# CW308T_PIC24FJ.net
KiCad netlist of a schematic drawn in Altium Designer
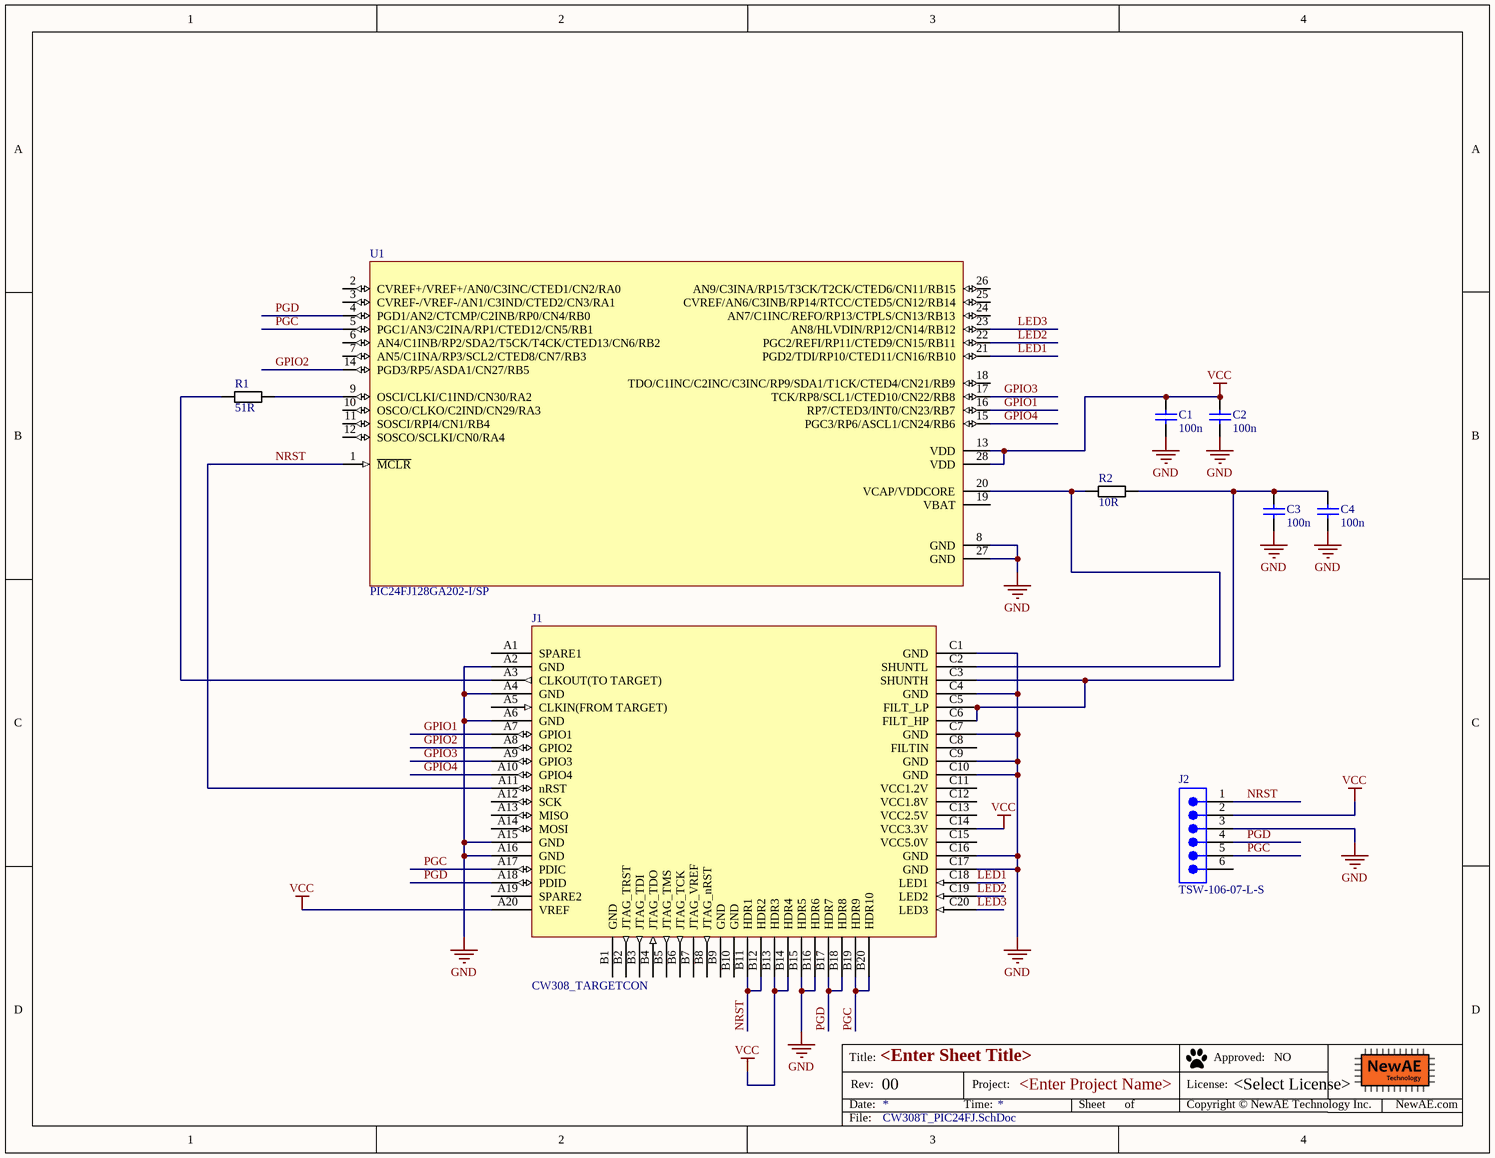
[diagram p0: CW308T_PIC24FJ.SchDoc]

(export (version "E")
  (design (tool "Eeschema 10.0.6"))
  (components
    (comp (ref "C1")
      (value "100n")
      (footprint "CAPC0603_M")
      (description "100n, 0603")
      (fields (field (name "PART NUMBER") "CCHIP-100n-0603"))
      (libsource (lib "NewAE_AltiumLib") (part "CAP"))
    )
    (comp (ref "C2")
      (value "100n")
      (footprint "CAPC0603_M")
      (description "100n, 0603")
      (fields (field (name "PART NUMBER") "CCHIP-100n-0603"))
      (libsource (lib "NewAE_AltiumLib") (part "CAP"))
    )
    (comp (ref "C3")
      (value "100n")
      (footprint "CAPC0603_M")
      (description "100n, 0603")
      (fields (field (name "PART NUMBER") "CCHIP-100n-0603"))
      (libsource (lib "NewAE_AltiumLib") (part "CAP"))
    )
    (comp (ref "C4")
      (value "100n")
      (footprint "CAPC0603_M")
      (description "100n, 0603")
      (fields (field (name "PART NUMBER") "CCHIP-100n-0603"))
      (libsource (lib "NewAE_AltiumLib") (part "CAP"))
    )
    (comp (ref "J1")
      (value "CW308_TARGETCON")
      (footprint "CW308_TBOARD_CONN")
      (description "CW308 \"Standard\" Target Board Connector")
      (fields (field (name "PART NUMBER") "CW308_TBOARD"))
      (libsource (lib "NewAE_AltiumLib") (part "CW308_TBOARD"))
    )
    (comp (ref "J2")
      (value "TSW-106-07-L-S")
      (footprint "SMTC-TSW-106-07-X-S")
      (fields (field (name "MANUFACTURER") "Samtec"))
      (libsource (lib "Altium Content Vault") (part "SMTC-TSW-106-X-X-S-X"))
    )
    (comp (ref "R1")
      (value "51R")
      (footprint "RESC1608X55N")
      (description "51R res, 0603, 1%, 1/10W")
      (fields (field (name "PART NUMBER") "RCHIP-51R-0603") (field (name "TOLERANCE") "1%"))
      (libsource (lib "NewAE_AltiumLib") (part "RES-EU"))
    )
    (comp (ref "R2")
      (value "10R")
      (footprint "RESC1608X55N")
      (description "10R res, 0603, 1%, 1/10W")
      (fields (field (name "PART NUMBER") "RCHIP-10R-0603") (field (name "TOLERANCE") "1%"))
      (libsource (lib "NewAE_AltiumLib") (part "RES-EU"))
    )
    (comp (ref "U1")
      (value "PIC24FJ128GA202-I/SP")
      (footprint "DIP28")
      (description "PIC24FJ, Hardware AES")
      (libsource (lib "NewAE_AltiumLib") (part "PIC24FJ128GA202_28pin"))
    )
  )
  (nets
    (net (code "1") (name "/GPIO1") (class "Default")
      (node (ref "J1") (pin "A7") (pinfunction "GPIO1_A7") (pintype "bidirectional"))
      (node (ref "U1") (pin "16") (pinfunction "RP7/CTED3/INT0/CN23/RB7_16") (pintype "bidirectional"))
    )
    (net (code "2") (name "/GPIO2") (class "Default")
      (node (ref "J1") (pin "A8") (pinfunction "GPIO2_A8") (pintype "bidirectional"))
      (node (ref "U1") (pin "14") (pinfunction "PGD3/RP5/ASDA1/CN27/RB5_14") (pintype "bidirectional"))
    )
    (net (code "3") (name "/GPIO3") (class "Default")
      (node (ref "J1") (pin "A9") (pinfunction "GPIO3_A9") (pintype "bidirectional"))
      (node (ref "U1") (pin "17") (pinfunction "TCK/RP8/SCL1/CTED10/CN22/RB8_17") (pintype "bidirectional"))
    )
    (net (code "4") (name "/GPIO4") (class "Default")
      (node (ref "J1") (pin "A10") (pinfunction "GPIO4_A10") (pintype "bidirectional"))
      (node (ref "U1") (pin "15") (pinfunction "PGC3/RP6/ASCL1/CN24/RB6_15") (pintype "bidirectional"))
    )
    (net (code "5") (name "/LED1") (class "Default")
      (node (ref "J1") (pin "C18") (pinfunction "LED1_C18") (pintype "input"))
      (node (ref "U1") (pin "21") (pinfunction "PGD2/TDI/RP10/CTED11/CN16/RB10_21") (pintype "bidirectional"))
    )
    (net (code "6") (name "/LED2") (class "Default")
      (node (ref "J1") (pin "C19") (pinfunction "LED2_C19") (pintype "input"))
      (node (ref "U1") (pin "22") (pinfunction "PGC2/REFI/RP11/CTED9/CN15/RB11_22") (pintype "bidirectional"))
    )
    (net (code "7") (name "/LED3") (class "Default")
      (node (ref "J1") (pin "C20") (pinfunction "LED3_C20") (pintype "input"))
      (node (ref "U1") (pin "23") (pinfunction "AN8/HLVDIN/RP12/CN14/RB12_23") (pintype "bidirectional"))
    )
    (net (code "8") (name "/NRST") (class "Default")
      (node (ref "J1") (pin "A11") (pinfunction "nRST_A11") (pintype "bidirectional"))
      (node (ref "J1") (pin "B11") (pinfunction "HDR1_B11") (pintype "passive"))
      (node (ref "J1") (pin "B12") (pinfunction "HDR2_B12") (pintype "passive"))
      (node (ref "J2") (pin "1") (pinfunction "1_1") (pintype "passive"))
      (node (ref "U1") (pin "1") (pinfunction "~{MCLR}_1") (pintype "input"))
    )
    (net (code "9") (name "/PGC") (class "Default")
      (node (ref "J1") (pin "A17") (pinfunction "PDIC_A17") (pintype "bidirectional"))
      (node (ref "J1") (pin "B19") (pinfunction "HDR9_B19") (pintype "passive"))
      (node (ref "J1") (pin "B20") (pinfunction "HDR10_B20") (pintype "passive"))
      (node (ref "J2") (pin "5") (pinfunction "5_5") (pintype "passive"))
      (node (ref "U1") (pin "5") (pinfunction "PGC1/AN3/C2INA/RP1/CTED12/CN5/RB1_5") (pintype "bidirectional"))
    )
    (net (code "10") (name "/PGD") (class "Default")
      (node (ref "J1") (pin "A18") (pinfunction "PDID_A18") (pintype "bidirectional"))
      (node (ref "J1") (pin "B17") (pinfunction "HDR7_B17") (pintype "passive"))
      (node (ref "J1") (pin "B18") (pinfunction "HDR8_B18") (pintype "passive"))
      (node (ref "J2") (pin "4") (pinfunction "4_4") (pintype "passive"))
      (node (ref "U1") (pin "4") (pinfunction "PGD1/AN2/CTCMP/C2INB/RP0/CN4/RB0_4") (pintype "bidirectional"))
    )
    (net (code "11") (name "GND") (class "Default")
      (node (ref "C1") (pin "2") (pinfunction "2_2") (pintype "passive"))
      (node (ref "C2") (pin "2") (pinfunction "2_2") (pintype "passive"))
      (node (ref "C3") (pin "2") (pinfunction "2_2") (pintype "passive"))
      (node (ref "C4") (pin "2") (pinfunction "2_2") (pintype "passive"))
      (node (ref "J1") (pin "A15") (pinfunction "GND_A15") (pintype "passive"))
      (node (ref "J1") (pin "A16") (pinfunction "GND_A16") (pintype "passive"))
      (node (ref "J1") (pin "A2") (pinfunction "GND_A2") (pintype "passive"))
      (node (ref "J1") (pin "A4") (pinfunction "GND_A4") (pintype "passive"))
      (node (ref "J1") (pin "A6") (pinfunction "GND_A6") (pintype "power_in"))
      (node (ref "J1") (pin "B15") (pinfunction "HDR5_B15") (pintype "passive"))
      (node (ref "J1") (pin "B16") (pinfunction "HDR6_B16") (pintype "passive"))
      (node (ref "J1") (pin "C1") (pinfunction "GND_C1") (pintype "power_in"))
      (node (ref "J1") (pin "C10") (pinfunction "GND_C10") (pintype "power_in"))
      (node (ref "J1") (pin "C16") (pinfunction "GND_C16") (pintype "power_in"))
      (node (ref "J1") (pin "C17") (pinfunction "GND_C17") (pintype "power_in"))
      (node (ref "J1") (pin "C4") (pinfunction "GND_C4") (pintype "power_in"))
      (node (ref "J1") (pin "C7") (pinfunction "GND_C7") (pintype "power_in"))
      (node (ref "J1") (pin "C9") (pinfunction "GND_C9") (pintype "power_in"))
      (node (ref "J2") (pin "3") (pinfunction "3_3") (pintype "passive"))
      (node (ref "U1") (pin "27") (pinfunction "GND_27") (pintype "power_in"))
      (node (ref "U1") (pin "8") (pinfunction "GND_8") (pintype "power_in"))
    )
    (net (code "12") (name "Net-(J1-CLKOUT(TO_TARGET))") (class "Default")
      (node (ref "J1") (pin "A3") (pinfunction "CLKOUT(TO_TARGET)_A3") (pintype "output"))
      (node (ref "R1") (pin "1") (pinfunction "1_1") (pintype "passive"))
    )
    (net (code "13") (name "Net-(J1-FILT_HP)") (class "Default")
      (node (ref "C3") (pin "1") (pinfunction "1_1") (pintype "passive"))
      (node (ref "C4") (pin "1") (pinfunction "1_1") (pintype "passive"))
      (node (ref "J1") (pin "C3") (pinfunction "SHUNTH_C3") (pintype "passive"))
      (node (ref "J1") (pin "C5") (pinfunction "FILT_LP_C5") (pintype "passive"))
      (node (ref "J1") (pin "C6") (pinfunction "FILT_HP_C6") (pintype "passive"))
      (node (ref "R2") (pin "2") (pinfunction "2_2") (pintype "passive"))
    )
    (net (code "14") (name "Net-(J1-SHUNTL)") (class "Default")
      (node (ref "J1") (pin "C2") (pinfunction "SHUNTL_C2") (pintype "passive"))
      (node (ref "R2") (pin "1") (pinfunction "1_1") (pintype "passive"))
      (node (ref "U1") (pin "20") (pinfunction "VCAP/VDDCORE_20") (pintype "passive"))
    )
    (net (code "15") (name "Net-(U1-OSCI{slash}CLKI{slash}C1IND{slash}CN30{slash}RA2)") (class "Default")
      (node (ref "R1") (pin "2") (pinfunction "2_2") (pintype "passive"))
      (node (ref "U1") (pin "9") (pinfunction "OSCI/CLKI/C1IND/CN30/RA2_9") (pintype "bidirectional"))
    )
    (net (code "16") (name "VCC") (class "Default")
      (node (ref "C1") (pin "1") (pinfunction "1_1") (pintype "passive"))
      (node (ref "C2") (pin "1") (pinfunction "1_1") (pintype "passive"))
      (node (ref "J1") (pin "A20") (pinfunction "VREF_A20") (pintype "tri_state"))
      (node (ref "J1") (pin "B13") (pinfunction "HDR3_B13") (pintype "passive"))
      (node (ref "J1") (pin "B14") (pinfunction "HDR4_B14") (pintype "passive"))
      (node (ref "J1") (pin "C14") (pinfunction "VCC3.3V_C14") (pintype "power_in"))
      (node (ref "J2") (pin "2") (pinfunction "2_2") (pintype "passive"))
      (node (ref "U1") (pin "13") (pinfunction "VDD_13") (pintype "power_in"))
      (node (ref "U1") (pin "28") (pinfunction "VDD_28") (pintype "power_in"))
    )
    (net (code "17") (name "unconnected-(J1-CLKIN(FROM_TARGET)-PadA5)") (class "Default")
      (node (ref "J1") (pin "A5") (pinfunction "CLKIN(FROM_TARGET)_A5") (pintype "input"))
    )
    (net (code "18") (name "unconnected-(J1-FILTIN-PadC8)") (class "Default")
      (node (ref "J1") (pin "C8") (pinfunction "FILTIN_C8") (pintype "passive"))
    )
    (net (code "19") (name "unconnected-(J1-GND-PadB1)") (class "Default")
      (node (ref "J1") (pin "B1") (pinfunction "GND_B1") (pintype "passive"))
    )
    (net (code "20") (name "unconnected-(J1-GND-PadB9)") (class "Default")
      (node (ref "J1") (pin "B9") (pinfunction "GND_B9") (pintype "passive"))
    )
    (net (code "21") (name "unconnected-(J1-GND-PadB10)") (class "Default")
      (node (ref "J1") (pin "B10") (pinfunction "GND_B10") (pintype "passive"))
    )
    (net (code "22") (name "unconnected-(J1-JTAG_TCK-PadB6)") (class "Default")
      (node (ref "J1") (pin "B6") (pinfunction "JTAG_TCK_B6") (pintype "output"))
    )
    (net (code "23") (name "unconnected-(J1-JTAG_TDI-PadB3)") (class "Default")
      (node (ref "J1") (pin "B3") (pinfunction "JTAG_TDI_B3") (pintype "output"))
    )
    (net (code "24") (name "unconnected-(J1-JTAG_TDO-PadB4)") (class "Default")
      (node (ref "J1") (pin "B4") (pinfunction "JTAG_TDO_B4") (pintype "input"))
    )
    (net (code "25") (name "unconnected-(J1-JTAG_TMS-PadB5)") (class "Default")
      (node (ref "J1") (pin "B5") (pinfunction "JTAG_TMS_B5") (pintype "output"))
    )
    (net (code "26") (name "unconnected-(J1-JTAG_TRST-PadB2)") (class "Default")
      (node (ref "J1") (pin "B2") (pinfunction "JTAG_TRST_B2") (pintype "output"))
    )
    (net (code "27") (name "unconnected-(J1-JTAG_VREF-PadB7)") (class "Default")
      (node (ref "J1") (pin "B7") (pinfunction "JTAG_VREF_B7") (pintype "tri_state"))
    )
    (net (code "28") (name "unconnected-(J1-JTAG_nRST-PadB8)") (class "Default")
      (node (ref "J1") (pin "B8") (pinfunction "JTAG_nRST_B8") (pintype "output"))
    )
    (net (code "29") (name "unconnected-(J1-MISO-PadA13)") (class "Default")
      (node (ref "J1") (pin "A13") (pinfunction "MISO_A13") (pintype "bidirectional"))
    )
    (net (code "30") (name "unconnected-(J1-MOSI-PadA14)") (class "Default")
      (node (ref "J1") (pin "A14") (pinfunction "MOSI_A14") (pintype "bidirectional"))
    )
    (net (code "31") (name "unconnected-(J1-SCK-PadA12)") (class "Default")
      (node (ref "J1") (pin "A12") (pinfunction "SCK_A12") (pintype "bidirectional"))
    )
    (net (code "32") (name "unconnected-(J1-SPARE1-PadA1)") (class "Default")
      (node (ref "J1") (pin "A1") (pinfunction "SPARE1_A1") (pintype "passive"))
    )
    (net (code "33") (name "unconnected-(J1-SPARE2-PadA19)") (class "Default")
      (node (ref "J1") (pin "A19") (pinfunction "SPARE2_A19") (pintype "passive"))
    )
    (net (code "34") (name "unconnected-(J1-VCC1.2V-PadC11)") (class "Default")
      (node (ref "J1") (pin "C11") (pinfunction "VCC1.2V_C11") (pintype "power_in"))
    )
    (net (code "35") (name "unconnected-(J1-VCC1.8V-PadC12)") (class "Default")
      (node (ref "J1") (pin "C12") (pinfunction "VCC1.8V_C12") (pintype "power_in"))
    )
    (net (code "36") (name "unconnected-(J1-VCC2.5V-PadC13)") (class "Default")
      (node (ref "J1") (pin "C13") (pinfunction "VCC2.5V_C13") (pintype "power_in"))
    )
    (net (code "37") (name "unconnected-(J1-VCC5.0V-PadC15)") (class "Default")
      (node (ref "J1") (pin "C15") (pinfunction "VCC5.0V_C15") (pintype "power_in"))
    )
    (net (code "38") (name "unconnected-(J2-Pad6)") (class "Default")
      (node (ref "J2") (pin "6") (pinfunction "6_6") (pintype "passive"))
    )
    (net (code "39") (name "unconnected-(U1-AN4{slash}C1INB{slash}RP2{slash}SDA2{slash}T5CK{slash}T4CK{slash}CTED13{slash}CN6{slash}RB2-Pad6)") (class "Default")
      (node (ref "U1") (pin "6") (pinfunction "AN4/C1INB/RP2/SDA2/T5CK/T4CK/CTED13/CN6/RB2_6") (pintype "bidirectional"))
    )
    (net (code "40") (name "unconnected-(U1-AN5{slash}C1INA{slash}RP3{slash}SCL2{slash}CTED8{slash}CN7{slash}RB3-Pad7)") (class "Default")
      (node (ref "U1") (pin "7") (pinfunction "AN5/C1INA/RP3/SCL2/CTED8/CN7/RB3_7") (pintype "bidirectional"))
    )
    (net (code "41") (name "unconnected-(U1-AN7{slash}C1INC{slash}REFO{slash}RP13{slash}CTPLS{slash}CN13{slash}RB13-Pad24)") (class "Default")
      (node (ref "U1") (pin "24") (pinfunction "AN7/C1INC/REFO/RP13/CTPLS/CN13/RB13_24") (pintype "bidirectional"))
    )
    (net (code "42") (name "unconnected-(U1-AN9{slash}C3INA{slash}RP15{slash}T3CK{slash}T2CK{slash}CTED6{slash}CN11{slash}RB15-Pad26)") (class "Default")
      (node (ref "U1") (pin "26") (pinfunction "AN9/C3INA/RP15/T3CK/T2CK/CTED6/CN11/RB15_26") (pintype "bidirectional"))
    )
    (net (code "43") (name "unconnected-(U1-CVREF+{slash}VREF+{slash}AN0{slash}C3INC{slash}CTED1{slash}CN2{slash}RA0-Pad2)") (class "Default")
      (node (ref "U1") (pin "2") (pinfunction "CVREF+/VREF+/AN0/C3INC/CTED1/CN2/RA0_2") (pintype "bidirectional"))
    )
    (net (code "44") (name "unconnected-(U1-CVREF-{slash}VREF-{slash}AN1{slash}C3IND{slash}CTED2{slash}CN3{slash}RA1-Pad3)") (class "Default")
      (node (ref "U1") (pin "3") (pinfunction "CVREF-/VREF-/AN1/C3IND/CTED2/CN3/RA1_3") (pintype "bidirectional"))
    )
    (net (code "45") (name "unconnected-(U1-CVREF{slash}AN6{slash}C3INB{slash}RP14{slash}RTCC{slash}CTED5{slash}CN12{slash}RB14-Pad25)") (class "Default")
      (node (ref "U1") (pin "25") (pinfunction "CVREF/AN6/C3INB/RP14/RTCC/CTED5/CN12/RB14_25") (pintype "bidirectional"))
    )
    (net (code "46") (name "unconnected-(U1-OSCO{slash}CLKO{slash}C2IND{slash}CN29{slash}RA3-Pad10)") (class "Default")
      (node (ref "U1") (pin "10") (pinfunction "OSCO/CLKO/C2IND/CN29/RA3_10") (pintype "bidirectional"))
    )
    (net (code "47") (name "unconnected-(U1-SOSCI{slash}RPI4{slash}CN1{slash}RB4-Pad11)") (class "Default")
      (node (ref "U1") (pin "11") (pinfunction "SOSCI/RPI4/CN1/RB4_11") (pintype "bidirectional"))
    )
    (net (code "48") (name "unconnected-(U1-SOSCO{slash}SCLKI{slash}CN0{slash}RA4-Pad12)") (class "Default")
      (node (ref "U1") (pin "12") (pinfunction "SOSCO/SCLKI/CN0/RA4_12") (pintype "bidirectional"))
    )
    (net (code "49") (name "unconnected-(U1-TDO{slash}C1INC{slash}C2INC{slash}C3INC{slash}RP9{slash}SDA1{slash}T1CK{slash}CTED4{slash}CN21{slash}RB9-Pad18)") (class "Default")
      (node (ref "U1") (pin "18") (pinfunction "TDO/C1INC/C2INC/C3INC/RP9/SDA1/T1CK/CTED4/CN21/RB9_18") (pintype "bidirectional"))
    )
    (net (code "50") (name "unconnected-(U1-VBAT-Pad19)") (class "Default")
      (node (ref "U1") (pin "19") (pinfunction "VBAT_19") (pintype "passive"))
    )
  )
)
